# System.net
KiCad netlist of a schematic drawn in Altium Designer
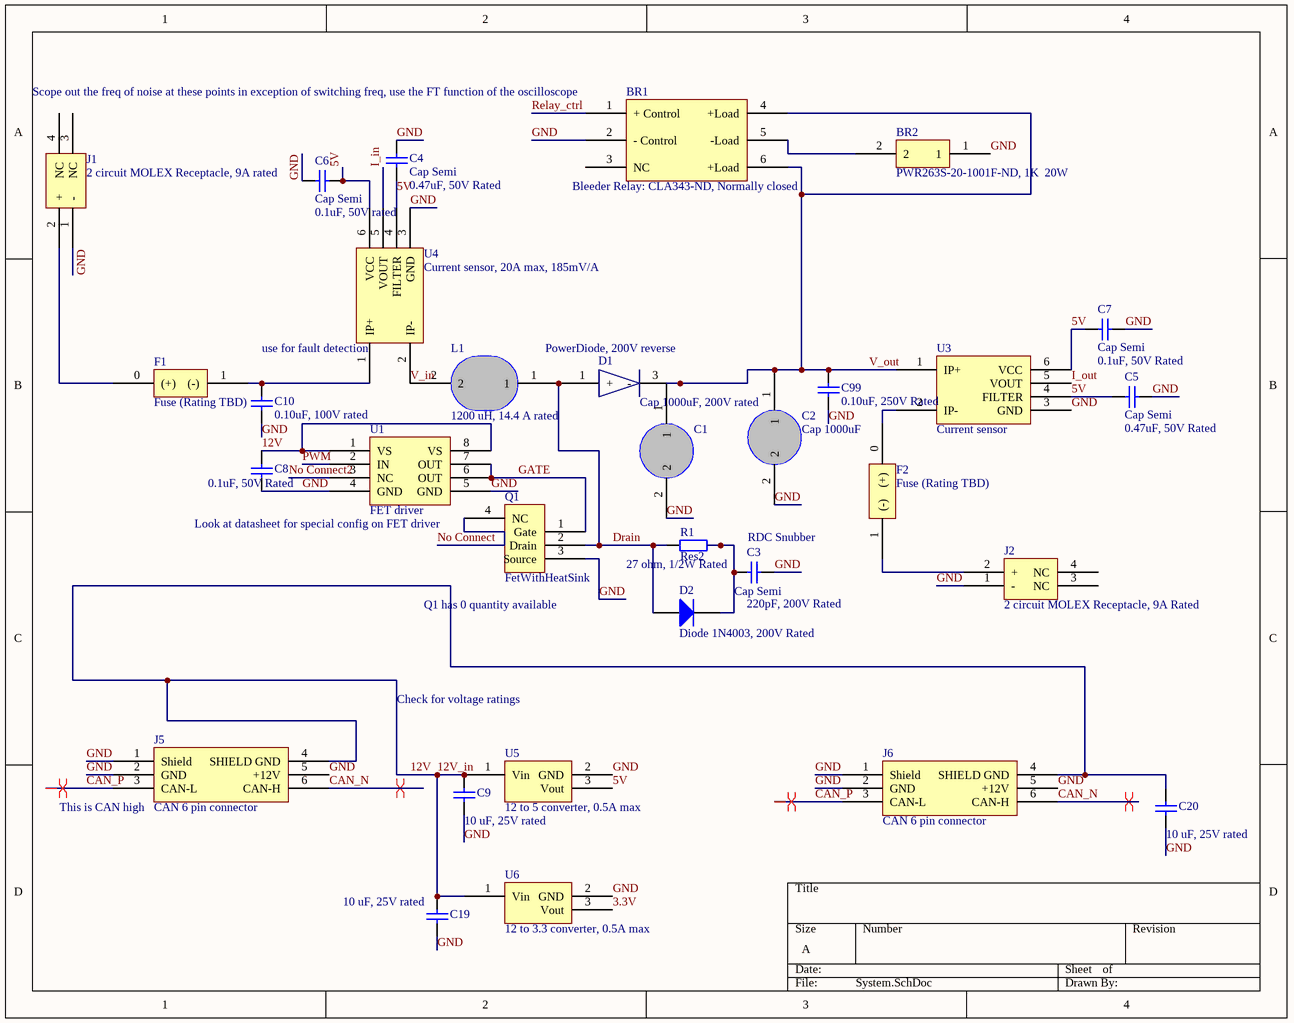
[diagram p0: System.SchDoc]

(export (version "E")
  (design (tool "Eeschema 10.0.6"))
  (components
    (comp (ref "BR1")
      (value "Bleeder Relay: CLA343-ND, Normally closed")
      (footprint "Bleeder Relay: CLA343-ND")
      (libsource (lib "Helianthus 2.1 Schematics") (part "Bleeder Relay{colon} CLA343-ND"))
    )
    (comp (ref "BR2")
      (value "PWR263S-20-1001F-ND, 1K  20W")
      (footprint "PWR263S-20-1001F-ND")
      (libsource (lib "Helianthus 2.1 Schematics") (part "PWR263S-20-1001F-ND"))
    )
    (comp (ref "C1")
      (value "Cap 1000uF, 200V rated")
      (footprint "LargeCap")
      (libsource (lib "Helianthus 2 Schematics") (part "Cap 1200uF"))
    )
    (comp (ref "C2")
      (value "Cap 1000uF")
      (footprint "LargeCap")
      (libsource (lib "Helianthus 2 Schematics") (part "Cap 1200uF"))
    )
    (comp (ref "C3")
      (value "Cap Semi")
      (footprint "C1206")
      (description "Capacitor (Semiconductor SIM Model)")
      (fields (field (name "ALTIUM_VALUE") "220pF, 200V Rated") (field (name "PUBLISHER") "Altium Limited"))
      (libsource (lib "Miscellaneous Devices") (part "Cap Semi"))
    )
    (comp (ref "C4")
      (value "Cap Semi")
      (footprint "C1206")
      (description "Capacitor (Semiconductor SIM Model)")
      (fields (field (name "ALTIUM_VALUE") "0.47uF, 50V Rated") (field (name "PUBLISHER") "Altium Limited"))
      (libsource (lib "Miscellaneous Devices") (part "Cap Semi"))
    )
    (comp (ref "C5")
      (value "Cap Semi")
      (footprint "C1206")
      (description "Capacitor (Semiconductor SIM Model)")
      (fields (field (name "ALTIUM_VALUE") "0.47uF, 50V Rated") (field (name "PUBLISHER") "Altium Limited"))
      (libsource (lib "Miscellaneous Devices") (part "Cap Semi"))
    )
    (comp (ref "C6")
      (value "Cap Semi")
      (footprint "C1206")
      (description "Capacitor (Semiconductor SIM Model)")
      (fields (field (name "ALTIUM_VALUE") "0.1uF, 50V rated") (field (name "PUBLISHER") "Altium Limited"))
      (libsource (lib "Miscellaneous Devices") (part "Cap Semi"))
    )
    (comp (ref "C7")
      (value "Cap Semi")
      (footprint "C1206")
      (description "Capacitor (Semiconductor SIM Model)")
      (fields (field (name "ALTIUM_VALUE") "0.1uF, 50V Rated") (field (name "PUBLISHER") "Altium Limited"))
      (libsource (lib "Miscellaneous Devices") (part "Cap Semi"))
    )
    (comp (ref "C8")
      (value "0.1uF, 50V Rated")
      (footprint "C1206")
      (description "Capacitor (Semiconductor SIM Model)")
      (fields (field (name "Comment") "Cap Semi") (field (name "PUBLISHER") "Altium Limited"))
      (libsource (lib "Miscellaneous Devices") (part "Cap Semi"))
    )
    (comp (ref "C9")
      (value "10 uF, 25V rated")
      (footprint "C1206")
      (description "Capacitor (Semiconductor SIM Model)")
      (fields (field (name "Comment") "Cap Semi") (field (name "PUBLISHER") "Altium Limited"))
      (libsource (lib "Miscellaneous Devices") (part "Cap Semi"))
    )
    (comp (ref "C10")
      (value "0.10uF, 100V rated")
      (footprint "C1210")
      (description "Capacitor (Semiconductor SIM Model)")
      (fields (field (name "Comment") "Cap Semi") (field (name "PUBLISHER") "Altium Limited"))
      (libsource (lib "Miscellaneous Devices") (part "Cap Semi"))
    )
    (comp (ref "C19")
      (value "10 uF, 25V rated")
      (footprint "C1206")
      (description "Capacitor (Semiconductor SIM Model)")
      (fields (field (name "Comment") "Cap Semi") (field (name "PUBLISHER") "Altium Limited"))
      (libsource (lib "Miscellaneous Devices") (part "Cap Semi"))
    )
    (comp (ref "C20")
      (value "10 uF, 25V rated")
      (footprint "C1206")
      (description "Capacitor (Semiconductor SIM Model)")
      (fields (field (name "Comment") "Cap Semi") (field (name "PUBLISHER") "Altium Limited"))
      (libsource (lib "Miscellaneous Devices") (part "Cap Semi"))
    )
    (comp (ref "C99")
      (value "0.10uF, 250V Rated")
      (footprint "C1210")
      (description "Capacitor (Semiconductor SIM Model)")
      (fields (field (name "Comment") "Cap Semi") (field (name "PUBLISHER") "Altium Limited"))
      (libsource (lib "Miscellaneous Devices") (part "Cap Semi"))
    )
    (comp (ref "D1")
      (value "PowerDiode, 200V reverse")
      (footprint "PowerDiode")
      (libsource (lib "Helianthus 2 Schematics") (part "PowerDiode"))
    )
    (comp (ref "D2")
      (value "Diode 1N4003, 200V Rated")
      (footprint "Diode RDC")
      (description "1 Amp General Purpose Rectifier")
      (fields (field (name "PUBLISHER") "Altium Limited"))
      (libsource (lib "Miscellaneous Devices") (part "Diode 1N4003"))
    )
    (comp (ref "F1")
      (value "Fuse (Rating TBD)")
      (footprint "Fuseholder")
      (libsource (lib "") (part "Fuseholder_1"))
    )
    (comp (ref "F2")
      (value "Fuse (Rating TBD)")
      (footprint "Fuseholder")
      (libsource (lib "Helianthus 2.1 Schematics") (part "Fuseholder"))
    )
    (comp (ref "J1")
      (value "2 circuit MOLEX Receptacle, 9A rated")
      (footprint "2 circuit MOLEX Receptacle")
      (libsource (lib "Helianthus 2 Schematics") (part "2 circuit MOLEX Receptacle"))
    )
    (comp (ref "J2")
      (value "2 circuit MOLEX Receptacle, 9A Rated")
      (footprint "2 circuit MOLEX Receptacle")
      (libsource (lib "") (part "2 circuit MOLEX Receptacle_1"))
    )
    (comp (ref "J5")
      (value "CAN 6 pin connector")
      (footprint "CAN 6 pin connector")
      (libsource (lib "Helianthus 2 Schematics") (part "CAN 6 pin connector"))
    )
    (comp (ref "J6")
      (value "CAN 6 pin connector")
      (footprint "CAN 6 pin connector")
      (libsource (lib "Helianthus 2 Schematics") (part "CAN 6 pin connector"))
    )
    (comp (ref "L1")
      (value "1200 uH, 14.4 A rated")
      (footprint "Large Inductor")
      (description "120 uH")
      (libsource (lib "Helianthus 2 Schematics") (part "Large inductor"))
    )
    (comp (ref "Q1")
      (value "FetWithHeatSink")
      (footprint "FetWithHeatSink")
      (libsource (lib "Helianthus 2 Schematics") (part "FetWithHeatSink"))
    )
    (comp (ref "R1")
      (value "Res2")
      (footprint "RES RDC")
      (description "Resistor")
      (fields (field (name "ALTIUM_VALUE") "27 ohm, 1/2W Rated") (field (name "PUBLISHER") "Altium Limited"))
      (libsource (lib "Miscellaneous Devices") (part "Res2"))
    )
    (comp (ref "U1")
      (value "FET driver")
      (footprint "FET Driver")
      (libsource (lib "Helianthus 2 Schematics") (part "FET driver"))
    )
    (comp (ref "U3")
      (value "Current sensor")
      (footprint "Current sensor")
      (description "This is the new current sensor 620-1262-1-ND")
      (libsource (lib "Helianthus 2 Schematics") (part "Current sensor"))
    )
    (comp (ref "U4")
      (value "Current sensor, 20A max, 185mV/A")
      (footprint "Current sensor")
      (libsource (lib "") (part "Current sensor_1"))
    )
    (comp (ref "U5")
      (value "12 to 5 converter, 0.5A max")
      (footprint "12 to 5 converter")
      (libsource (lib "Helianthus 2 Schematics") (part "12 to 5 converter"))
    )
    (comp (ref "U6")
      (value "12 to 3.3 converter, 0.5A max")
      (footprint "12 to 5 converter")
      (libsource (lib "Helianthus 2 Schematics") (part "12 to 5 converter"))
    )
  )
  (nets
    (net (code "1") (name "/3.3V") (class "Default")
      (node (ref "U6") (pin "3") (pinfunction "Vout_3") (pintype "passive"))
    )
    (net (code "2") (name "/5V") (class "Default")
      (node (ref "C4") (pin "1") (pinfunction "1_1") (pintype "passive"))
      (node (ref "C5") (pin "1") (pinfunction "1_1") (pintype "passive"))
      (node (ref "C6") (pin "1") (pinfunction "1_1") (pintype "passive"))
      (node (ref "C7") (pin "1") (pinfunction "1_1") (pintype "passive"))
      (node (ref "U3") (pin "4") (pinfunction "FILTER_4") (pintype "passive"))
      (node (ref "U3") (pin "6") (pinfunction "VCC_6") (pintype "passive"))
      (node (ref "U4") (pin "4") (pinfunction "FILTER_4") (pintype "passive"))
      (node (ref "U4") (pin "6") (pinfunction "VCC_6") (pintype "passive"))
      (node (ref "U5") (pin "3") (pinfunction "Vout_3") (pintype "passive"))
    )
    (net (code "3") (name "/12V") (class "Default")
      (node (ref "C19") (pin "2") (pinfunction "2_2") (pintype "passive"))
      (node (ref "C20") (pin "2") (pinfunction "2_2") (pintype "passive"))
      (node (ref "C8") (pin "1") (pinfunction "1_1") (pintype "passive"))
      (node (ref "C9") (pin "2") (pinfunction "2_2") (pintype "passive"))
      (node (ref "J5") (pin "4") (pinfunction "SHIELD_GND_4") (pintype "passive"))
      (node (ref "J6") (pin "4") (pinfunction "SHIELD_GND_4") (pintype "passive"))
      (node (ref "U1") (pin "1") (pinfunction "VS_1") (pintype "passive"))
      (node (ref "U1") (pin "8") (pinfunction "VS_8") (pintype "passive"))
      (node (ref "U5") (pin "1") (pinfunction "Vin_1") (pintype "passive"))
      (node (ref "U6") (pin "1") (pinfunction "Vin_1") (pintype "passive"))
    )
    (net (code "4") (name "/CAN_N") (class "Default")
      (node (ref "J5") (pin "6") (pinfunction "CAN-H_6") (pintype "passive"))
      (node (ref "J6") (pin "6") (pinfunction "CAN-H_6") (pintype "passive"))
    )
    (net (code "5") (name "/CAN_P") (class "Default")
      (node (ref "J5") (pin "3") (pinfunction "CAN-L_3") (pintype "passive"))
      (node (ref "J6") (pin "3") (pinfunction "CAN-L_3") (pintype "passive"))
    )
    (net (code "6") (name "/Drain") (class "Default")
      (node (ref "D1") (pin "1") (pinfunction "+_1") (pintype "passive"))
      (node (ref "D2") (pin "1") (pinfunction "A_1") (pintype "passive"))
      (node (ref "L1") (pin "1") (pinfunction "1_1") (pintype "passive"))
      (node (ref "Q1") (pin "2") (pinfunction "Drain_2") (pintype "passive"))
      (node (ref "R1") (pin "1") (pinfunction "1_1") (pintype "passive"))
    )
    (net (code "7") (name "/GATE") (class "Default")
      (node (ref "Q1") (pin "1") (pinfunction "Gate_1") (pintype "passive"))
      (node (ref "U1") (pin "6") (pinfunction "OUT_6") (pintype "passive"))
      (node (ref "U1") (pin "7") (pinfunction "OUT_7") (pintype "passive"))
    )
    (net (code "8") (name "/GND") (class "Default")
      (node (ref "BR1") (pin "2") (pinfunction "-_Control_2") (pintype "passive"))
      (node (ref "BR2") (pin "1") (pinfunction "1_1") (pintype "passive"))
      (node (ref "C1") (pin "2") (pinfunction "2_2") (pintype "passive"))
      (node (ref "C10") (pin "2") (pinfunction "2_2") (pintype "passive"))
      (node (ref "C19") (pin "1") (pinfunction "1_1") (pintype "passive"))
      (node (ref "C2") (pin "2") (pinfunction "2_2") (pintype "passive"))
      (node (ref "C20") (pin "1") (pinfunction "1_1") (pintype "passive"))
      (node (ref "C3") (pin "2") (pinfunction "2_2") (pintype "passive"))
      (node (ref "C4") (pin "2") (pinfunction "2_2") (pintype "passive"))
      (node (ref "C5") (pin "2") (pinfunction "2_2") (pintype "passive"))
      (node (ref "C6") (pin "2") (pinfunction "2_2") (pintype "passive"))
      (node (ref "C7") (pin "2") (pinfunction "2_2") (pintype "passive"))
      (node (ref "C8") (pin "2") (pinfunction "2_2") (pintype "passive"))
      (node (ref "C9") (pin "1") (pinfunction "1_1") (pintype "passive"))
      (node (ref "C99") (pin "1") (pinfunction "1_1") (pintype "passive"))
      (node (ref "J1") (pin "1") (pinfunction "-_1") (pintype "passive"))
      (node (ref "J2") (pin "1") (pinfunction "-_1") (pintype "passive"))
      (node (ref "J5") (pin "1") (pinfunction "Shield_1") (pintype "passive"))
      (node (ref "J5") (pin "2") (pinfunction "GND_2") (pintype "passive"))
      (node (ref "J5") (pin "5") (pinfunction "+12V_5") (pintype "passive"))
      (node (ref "J6") (pin "1") (pinfunction "Shield_1") (pintype "passive"))
      (node (ref "J6") (pin "2") (pinfunction "GND_2") (pintype "passive"))
      (node (ref "J6") (pin "5") (pinfunction "+12V_5") (pintype "passive"))
      (node (ref "Q1") (pin "3") (pinfunction "Source_3") (pintype "passive"))
      (node (ref "U1") (pin "4") (pinfunction "GND_4") (pintype "passive"))
      (node (ref "U1") (pin "5") (pinfunction "GND_5") (pintype "passive"))
      (node (ref "U3") (pin "3") (pinfunction "GND_3") (pintype "passive"))
      (node (ref "U4") (pin "3") (pinfunction "GND_3") (pintype "passive"))
      (node (ref "U5") (pin "2") (pinfunction "GND_2") (pintype "passive"))
      (node (ref "U6") (pin "2") (pinfunction "GND_2") (pintype "passive"))
    )
    (net (code "9") (name "/I_in") (class "Default")
      (node (ref "U4") (pin "5") (pinfunction "VOUT_5") (pintype "passive"))
    )
    (net (code "10") (name "/I_out") (class "Default")
      (node (ref "U3") (pin "5") (pinfunction "VOUT_5") (pintype "passive"))
    )
    (net (code "11") (name "/No Connect") (class "Default")
      (node (ref "Q1") (pin "4") (pinfunction "NC_4") (pintype "passive"))
    )
    (net (code "12") (name "/No Connect2") (class "Default")
      (node (ref "U1") (pin "3") (pinfunction "NC_3") (pintype "passive"))
    )
    (net (code "13") (name "/PWM") (class "Default")
      (node (ref "U1") (pin "2") (pinfunction "IN_2") (pintype "passive"))
    )
    (net (code "14") (name "/Relay_ctrl") (class "Default")
      (node (ref "BR1") (pin "1") (pinfunction "+_Control_1") (pintype "passive"))
    )
    (net (code "15") (name "/V_in") (class "Default")
      (node (ref "L1") (pin "2") (pinfunction "2_2") (pintype "passive"))
      (node (ref "U4") (pin "2") (pinfunction "IP-_2") (pintype "passive"))
    )
    (net (code "16") (name "/V_out") (class "Default")
      (node (ref "BR1") (pin "4") (pinfunction "+Load_4") (pintype "passive"))
      (node (ref "BR1") (pin "6") (pinfunction "+Load_6") (pintype "passive"))
      (node (ref "C1") (pin "1") (pinfunction "1_1") (pintype "passive"))
      (node (ref "C2") (pin "1") (pinfunction "1_1") (pintype "passive"))
      (node (ref "C99") (pin "2") (pinfunction "2_2") (pintype "passive"))
      (node (ref "D1") (pin "3") (pinfunction "-_3") (pintype "passive"))
      (node (ref "U3") (pin "1") (pinfunction "IP+_1") (pintype "passive"))
    )
    (net (code "17") (name "Net-(BR1--Load)") (class "Default")
      (node (ref "BR1") (pin "5") (pinfunction "-Load_5") (pintype "passive"))
      (node (ref "BR2") (pin "2") (pinfunction "2_2") (pintype "passive"))
    )
    (net (code "18") (name "Net-(D2-K)") (class "Default")
      (node (ref "C3") (pin "1") (pinfunction "1_1") (pintype "passive"))
      (node (ref "D2") (pin "2") (pinfunction "K_2") (pintype "passive"))
      (node (ref "R1") (pin "2") (pinfunction "2_2") (pintype "passive"))
    )
    (net (code "19") (name "Net-(F1-(+))") (class "Default")
      (node (ref "F1") (pin "0") (pinfunction "(+)_0") (pintype "passive"))
      (node (ref "J1") (pin "2") (pinfunction "+_2") (pintype "passive"))
    )
    (net (code "20") (name "Net-(F1-(-))") (class "Default")
      (node (ref "C10") (pin "1") (pinfunction "1_1") (pintype "passive"))
      (node (ref "F1") (pin "1") (pinfunction "(-)_1") (pintype "passive"))
      (node (ref "U4") (pin "1") (pinfunction "IP+_1") (pintype "passive"))
    )
    (net (code "21") (name "Net-(F2-(+))") (class "Default")
      (node (ref "F2") (pin "0") (pinfunction "(+)_0") (pintype "passive"))
      (node (ref "U3") (pin "2") (pinfunction "IP-_2") (pintype "passive"))
    )
    (net (code "22") (name "Net-(F2-(-))") (class "Default")
      (node (ref "F2") (pin "1") (pinfunction "(-)_1") (pintype "passive"))
      (node (ref "J2") (pin "2") (pinfunction "+_2") (pintype "passive"))
    )
    (net (code "23") (name "unconnected-(BR1-NC-Pad3)") (class "Default")
      (node (ref "BR1") (pin "3") (pinfunction "NC_3") (pintype "passive"))
    )
    (net (code "24") (name "unconnected-(J1-NC-Pad3)") (class "Default")
      (node (ref "J1") (pin "3") (pinfunction "NC_3") (pintype "passive"))
    )
    (net (code "25") (name "unconnected-(J1-NC-Pad4)") (class "Default")
      (node (ref "J1") (pin "4") (pinfunction "NC_4") (pintype "passive"))
    )
    (net (code "26") (name "unconnected-(J2-NC-Pad3)") (class "Default")
      (node (ref "J2") (pin "3") (pinfunction "NC_3") (pintype "passive"))
    )
    (net (code "27") (name "unconnected-(J2-NC-Pad4)") (class "Default")
      (node (ref "J2") (pin "4") (pinfunction "NC_4") (pintype "passive"))
    )
  )
)
